# AUDIO_1.net
KiCad netlist of a schematic drawn in Altium Designer
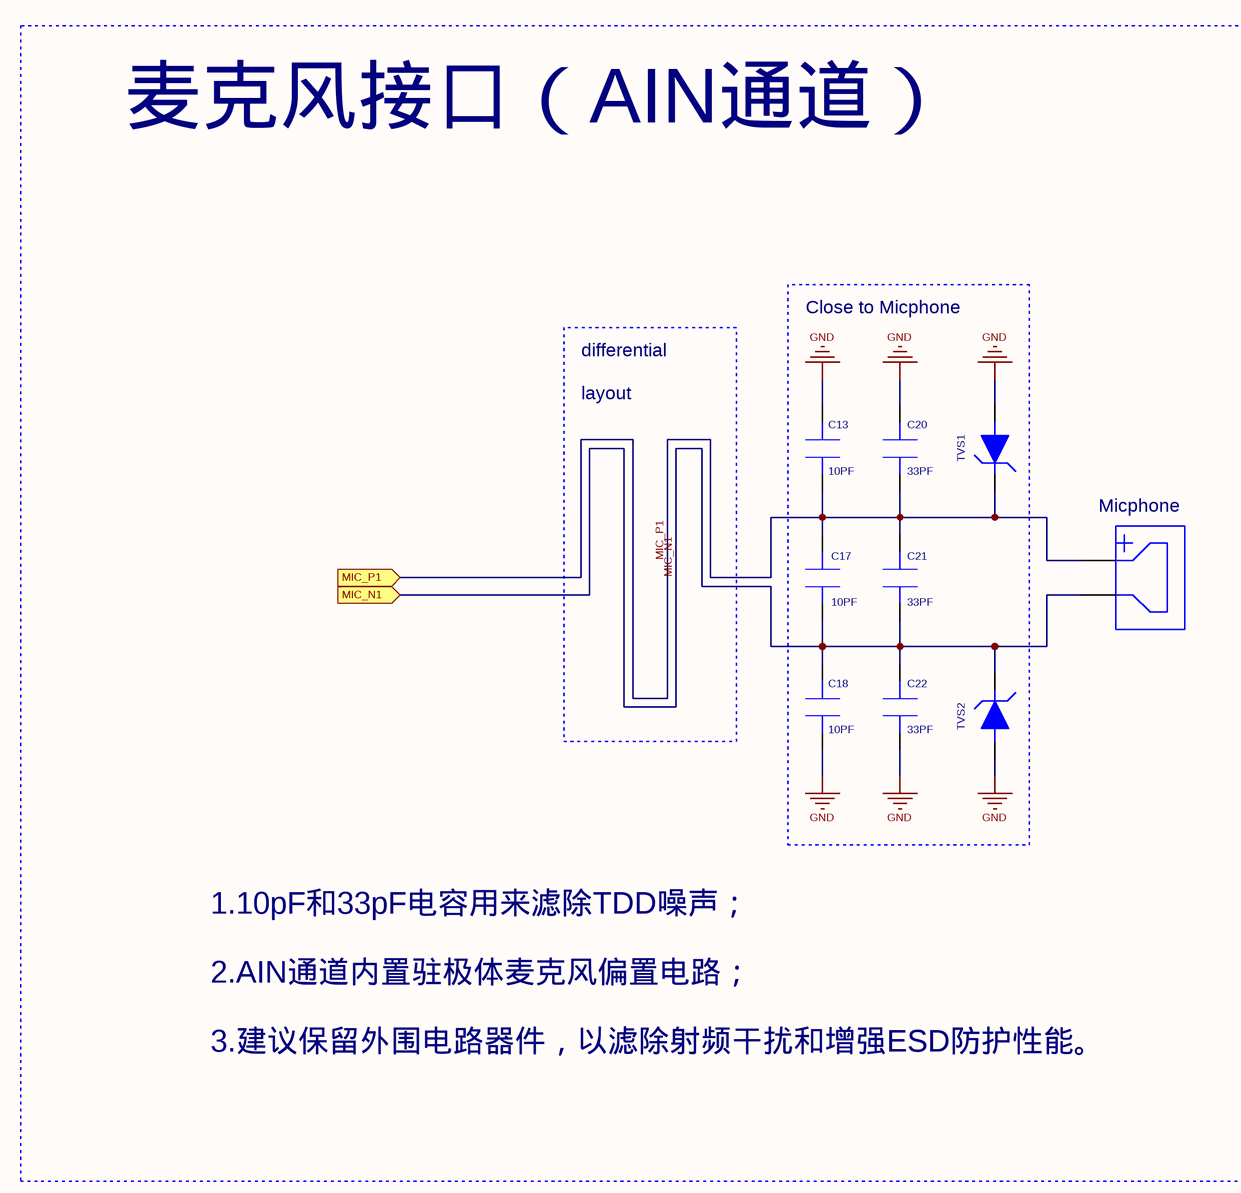
[diagram p0: AUDIO_1.SchDoc, top left]
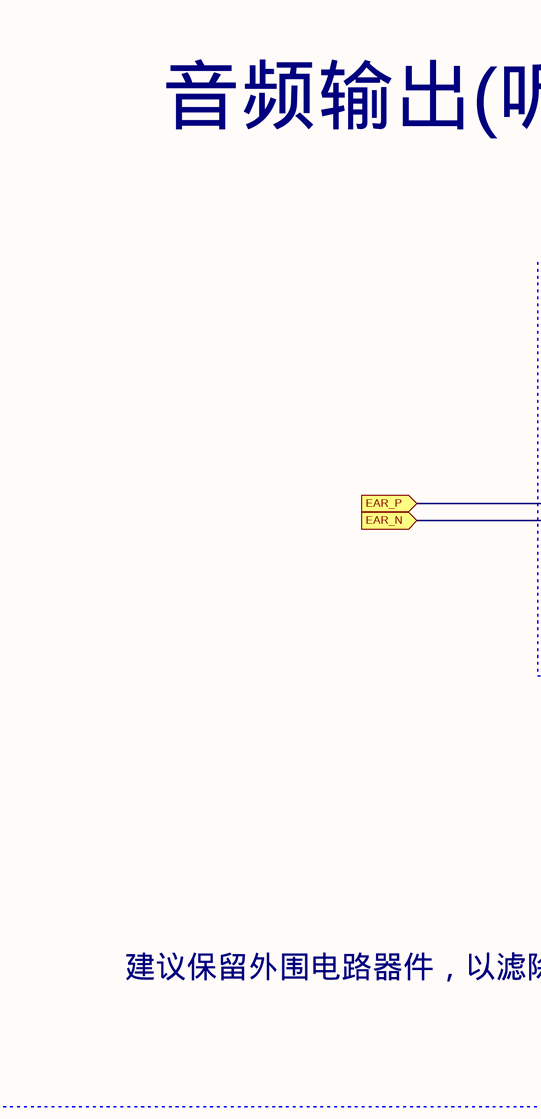
[diagram p1: AUDIO_1.SchDoc, top middle]
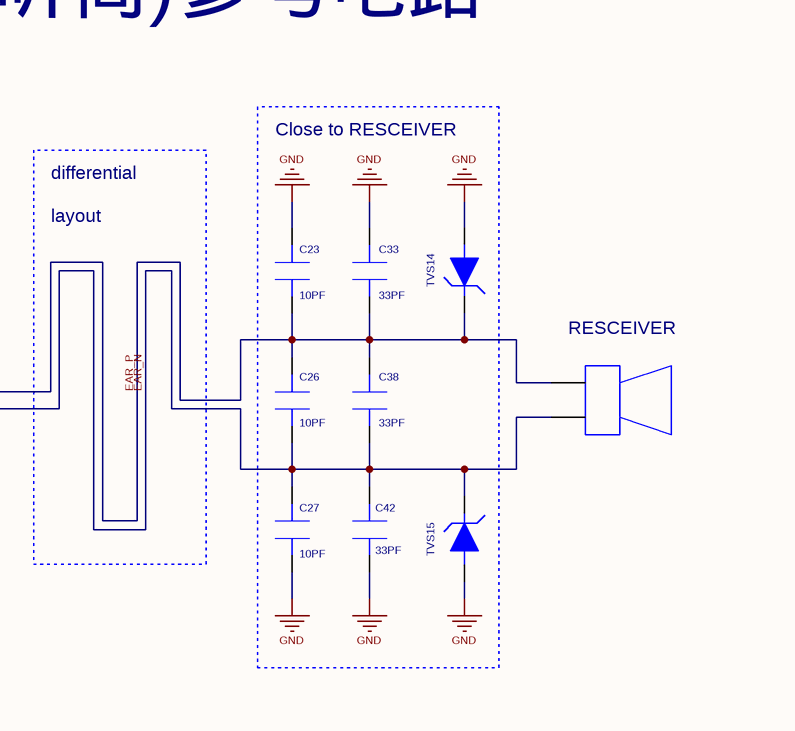
[diagram p2: AUDIO_1.SchDoc, top right]
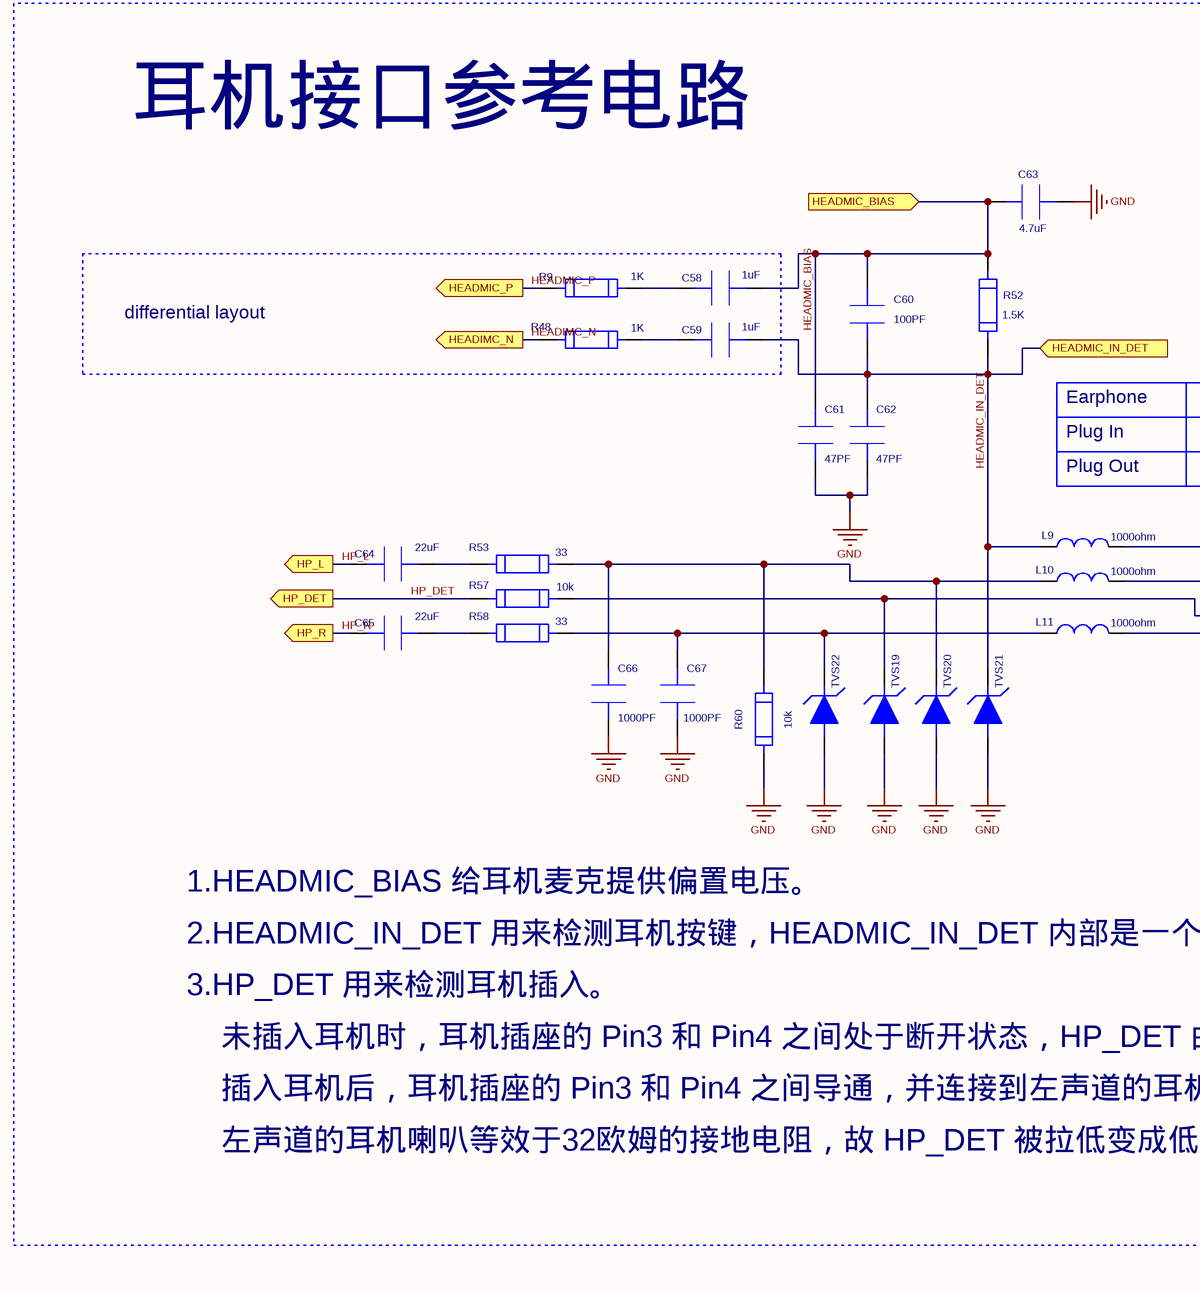
[diagram p3: AUDIO_1.SchDoc, bottom left]
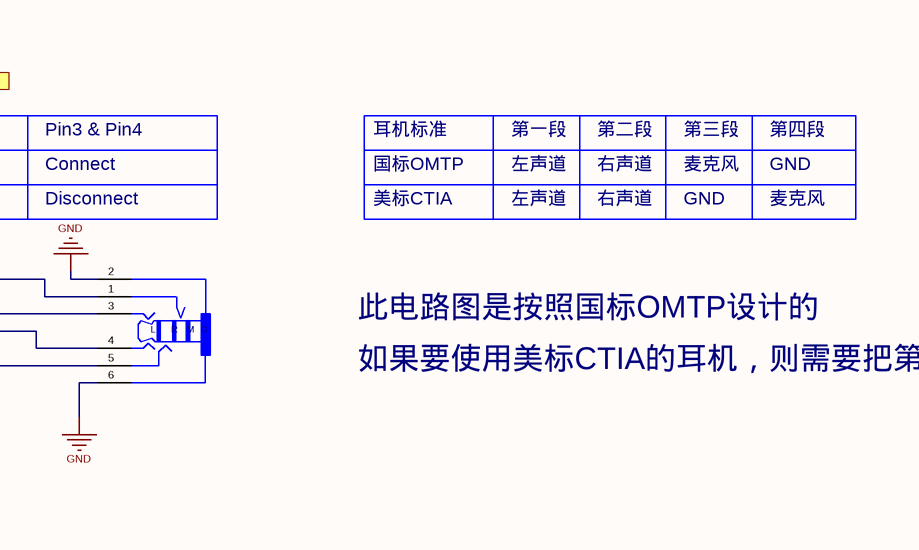
[diagram p4: AUDIO_1.SchDoc, bottom middle]
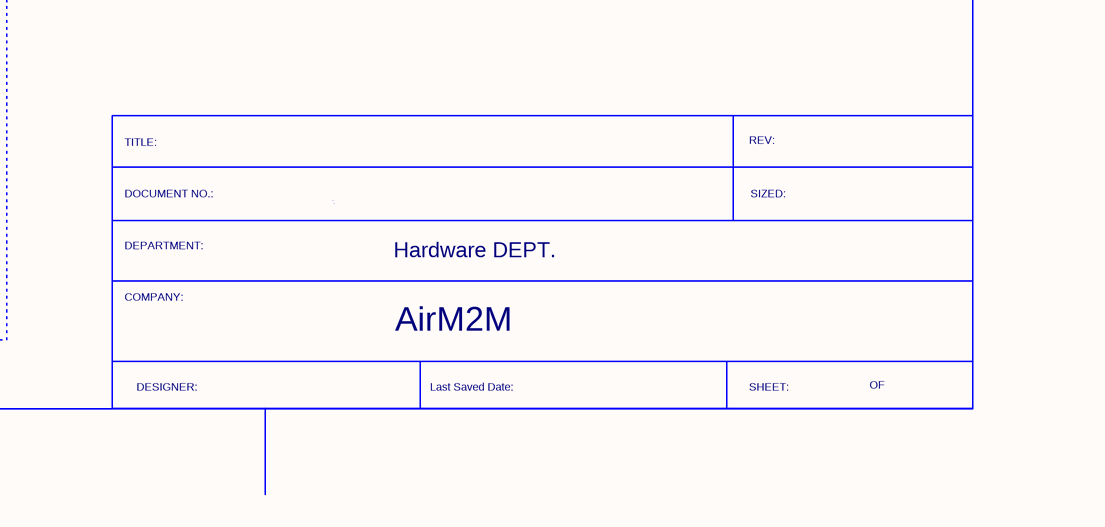
[diagram p5: AUDIO_1.SchDoc, bottom right]

(export (version "E")
  (design (tool "Eeschema 10.0.6"))
  (components
    (comp (ref "C13")
      (value "10PF")
      (footprint "SC0201")
      (description "CAP CER C0G;10PF;+/-5%;25V;0201;0.35mm;ROHS")
      (fields (field (name "TOLERANCE") "+/-5%") (field (name "Comment") "CAP-10PF-0201-COG"))
      (libsource (lib "*") (part "CAP-10PF-0201-COG"))
    )
    (comp (ref "C17")
      (value "10PF")
      (footprint "SC0201")
      (description "CAP CER C0G;10PF;+/-5%;25V;0201;0.35mm;ROHS")
      (fields (field (name "TOLERANCE") "+/-5%") (field (name "Comment") "CAP-10PF-0201-COG"))
      (libsource (lib "*") (part "CAP-10PF-0201-COG"))
    )
    (comp (ref "C18")
      (value "10PF")
      (footprint "SC0201")
      (description "CAP CER C0G;10PF;+/-5%;25V;0201;0.35mm;ROHS")
      (fields (field (name "TOLERANCE") "+/-5%") (field (name "Comment") "CAP-10PF-0201-COG"))
      (libsource (lib "*") (part "CAP-10PF-0201-COG"))
    )
    (comp (ref "C20")
      (value "33PF")
      (footprint "SC0201")
      (description "CAP CER C0G;10PF;+/-5%;25V;0201;0.35mm;ROHS")
      (fields (field (name "TOLERANCE") "+/-5%") (field (name "Comment") "CAP-10PF-0201-COG"))
      (libsource (lib "*") (part "CAP-10PF-0201-COG"))
    )
    (comp (ref "C21")
      (value "33PF")
      (footprint "SC0201")
      (description "CAP CER C0G;10PF;+/-5%;25V;0201;0.35mm;ROHS")
      (fields (field (name "TOLERANCE") "+/-5%") (field (name "Comment") "CAP-10PF-0201-COG"))
      (libsource (lib "*") (part "CAP-10PF-0201-COG"))
    )
    (comp (ref "C22")
      (value "33PF")
      (footprint "SC0201")
      (description "CAP CER C0G;10PF;+/-5%;25V;0201;0.35mm;ROHS")
      (fields (field (name "TOLERANCE") "+/-5%") (field (name "Comment") "CAP-10PF-0201-COG"))
      (libsource (lib "*") (part "CAP-10PF-0201-COG"))
    )
    (comp (ref "C23")
      (value "10PF")
      (footprint "SC0201")
      (description "CAP CER C0G;10PF;+/-5%;25V;0201;0.35mm;ROHS")
      (fields (field (name "TOLERANCE") "+/-5%") (field (name "Comment") "CAP-10PF-0201-COG"))
      (libsource (lib "*") (part "CAP-10PF-0201-COG"))
    )
    (comp (ref "C26")
      (value "10PF")
      (footprint "SC0201")
      (description "CAP CER C0G;10PF;+/-5%;25V;0201;0.35mm;ROHS")
      (fields (field (name "TOLERANCE") "+/-5%") (field (name "Comment") "CAP-10PF-0201-COG"))
      (libsource (lib "*") (part "CAP-10PF-0201-COG"))
    )
    (comp (ref "C27")
      (value "10PF")
      (footprint "SC0201")
      (description "CAP CER C0G;10PF;+/-5%;25V;0201;0.35mm;ROHS")
      (fields (field (name "TOLERANCE") "+/-5%") (field (name "Comment") "CAP-10PF-0201-COG"))
      (libsource (lib "*") (part "CAP-10PF-0201-COG"))
    )
    (comp (ref "C33")
      (value "33PF")
      (footprint "SC0201")
      (description "CAP CER C0G;10PF;+/-5%;25V;0201;0.35mm;ROHS")
      (fields (field (name "TOLERANCE") "+/-5%") (field (name "Comment") "CAP-10PF-0201-COG"))
      (libsource (lib "*") (part "CAP-10PF-0201-COG"))
    )
    (comp (ref "C38")
      (value "33PF")
      (footprint "SC0201")
      (description "CAP CER C0G;10PF;+/-5%;25V;0201;0.35mm;ROHS")
      (fields (field (name "TOLERANCE") "+/-5%") (field (name "Comment") "CAP-10PF-0201-COG"))
      (libsource (lib "*") (part "CAP-10PF-0201-COG"))
    )
    (comp (ref "C42")
      (value "33PF")
      (footprint "SC0201")
      (description "CAP CER C0G;10PF;+/-5%;25V;0201;0.35mm;ROHS")
      (fields (field (name "TOLERANCE") "+/-5%") (field (name "Comment") "CAP-10PF-0201-COG"))
      (libsource (lib "*") (part "CAP-10PF-0201-COG"))
    )
    (comp (ref "C58")
      (value "1uF")
      (footprint "SC0402")
      (description "CAP CER X5R;1uF;+/-10%;6.3V;0402;0.5mm;ROHS")
      (fields (field (name "TOLERANCE") "+/-10%") (field (name "Comment") "CAP-1UF-0402-X5R"))
      (libsource (lib "*") (part "CAP-1UF-0402-X5R"))
    )
    (comp (ref "C59")
      (value "1uF")
      (footprint "SC0402")
      (description "CAP CER X5R;1uF;+/-10%;6.3V;0402;0.5mm;ROHS")
      (fields (field (name "TOLERANCE") "+/-10%") (field (name "Comment") "CAP-1UF-0402-X5R"))
      (libsource (lib "*") (part "CAP-1UF-0402-X5R"))
    )
    (comp (ref "C60")
      (value "100PF")
      (footprint "SC0402")
      (description "CAP CER C0G;100PF;+/-5%;50V;0402;0.5mm;ROHS")
      (fields (field (name "TOLERANCE") "+/-5%") (field (name "Comment") "CAP-100PF-0402-C0G"))
      (libsource (lib "*") (part "CAP-100PF-0402-C0G"))
    )
    (comp (ref "C61")
      (value "47PF")
      (footprint "SC0402")
      (description "CAP CER C0G;47PF;+/-5%;50V;0402;0.5mm;ROHS")
      (fields (field (name "TOLERANCE") "+/-5%") (field (name "Comment") "CAP-47PF-0402-C0G"))
      (libsource (lib "*") (part "CAP-47PF-0402-C0G"))
    )
    (comp (ref "C62")
      (value "47PF")
      (footprint "SC0402")
      (description "CAP CER C0G;47PF;+/-5%;50V;0402;0.5mm;ROHS")
      (fields (field (name "TOLERANCE") "+/-5%") (field (name "Comment") "CAP-47PF-0402-C0G"))
      (libsource (lib "*") (part "CAP-47PF-0402-C0G"))
    )
    (comp (ref "C63")
      (value "4.7uF")
      (footprint "SC0402")
      (description "CAP CER;4.7uF;20%;6.3V;0402")
      (fields (field (name "TOLERANCE") "+/-20%") (field (name "Comment") "CAP-4.7UF-6.3V-0402"))
      (libsource (lib "*") (part "CAP-4.7UF-6.3V-0402"))
    )
    (comp (ref "C64")
      (value "22uF")
      (footprint "SC0402")
      (description "CAP CER;10uF;20%;6.3V")
      (fields (field (name "TOLERANCE") "+/-20%") (field (name "Comment") "CAP-10UF-6.3V-0402"))
      (libsource (lib "*") (part "CAP-10UF-6.3V-0402"))
    )
    (comp (ref "C65")
      (value "22uF")
      (footprint "SC0402")
      (description "CAP CER;10uF;20%;6.3V")
      (fields (field (name "TOLERANCE") "+/-20%") (field (name "Comment") "CAP-10UF-6.3V-0402"))
      (libsource (lib "*") (part "CAP-10UF-6.3V-0402"))
    )
    (comp (ref "C66")
      (value "1000PF")
      (footprint "SC0402")
      (description "CAP CER X7R;1000PF;+/-10%;50V;0402;0.5mm;ROHS")
      (fields (field (name "TOLERANCE") "+/-10%") (field (name "Comment") "CAP-1000PF-0402-X7R"))
      (libsource (lib "*") (part "CAP-1000PF-0402-X7R"))
    )
    (comp (ref "C67")
      (value "1000PF")
      (footprint "SC0402")
      (description "CAP CER X7R;1000PF;+/-10%;50V;0402;0.5mm;ROHS")
      (fields (field (name "TOLERANCE") "+/-10%") (field (name "Comment") "CAP-1000PF-0402-X7R"))
      (libsource (lib "*") (part "CAP-1000PF-0402-X7R"))
    )
    (comp (ref "J3")
      (value "AUDIO-SUGGEST-1")
      (footprint "AUDIO-EAR-DA0635180-1208-A")
      (description "耳机座")
      (libsource (lib "*") (part "AUDIO-SUGGEST-1"))
    )
    (comp (ref "J5")
      (value "AUDIO-SPEAKER-BLUEHY")
      (footprint "CON2-2")
      (libsource (lib "*") (part "AUDIO-SPEAKER-BLUEHY"))
    )
    (comp (ref "L9")
      (value "1000ohm")
      (footprint "SL0402")
      (description "Bead;1000ohm;250mA;0402;0.6mm;ROHS")
      (fields (field (name "Comment") "BEAD-1000OHM-0402"))
      (libsource (lib "*") (part "BEAD-1000OHM-0402"))
    )
    (comp (ref "L10")
      (value "1000ohm")
      (footprint "SL0402")
      (description "Bead;1000ohm;250mA;0402;0.6mm;ROHS")
      (fields (field (name "Comment") "BEAD-1000OHM-0402"))
      (libsource (lib "*") (part "BEAD-1000OHM-0402"))
    )
    (comp (ref "L11")
      (value "1000ohm")
      (footprint "SL0402")
      (description "Bead;1000ohm;250mA;0402;0.6mm;ROHS")
      (fields (field (name "Comment") "BEAD-1000OHM-0402"))
      (libsource (lib "*") (part "BEAD-1000OHM-0402"))
    )
    (comp (ref "M1")
      (value "AUDIO-MIC-BLUEHY")
      (footprint "CON2-2/3")
      (libsource (lib "*") (part "AUDIO-MIC-BLUEHY"))
    )
    (comp (ref "R9")
      (value "1K")
      (footprint "SR0402")
      (description "RES FILM;1K;+/-5%;1/16W;0402;0.4mm;ROHS")
      (fields (field (name "TOLERANCE") "+/-5%") (field (name "Comment") "RES-1K-0402"))
      (libsource (lib "*") (part "RES-1K-0402"))
    )
    (comp (ref "R48")
      (value "1K")
      (footprint "SR0402")
      (description "RES FILM;1K;+/-1%;1/16W;0402;0.4mm;ROHS")
      (fields (field (name "TOLERANCE") "+/-1%") (field (name "Comment") "RES-1K-+-1%-0402"))
      (libsource (lib "*") (part "RES-1K-+-1%-0402"))
    )
    (comp (ref "R52")
      (value "1.5K")
      (footprint "SR0402")
      (description "RES FILM;1.2k;+/-5%;1/16W;0402;0.4mm;ROHS")
      (fields (field (name "TOLERANCE") "5%") (field (name "Comment") "RES-1.2K-0402"))
      (libsource (lib "*") (part "RES-1.2K-0402"))
    )
    (comp (ref "R53")
      (value "33")
      (footprint "SR0402")
      (description "RES FILM;33;+/-5%;1/16W;0402;0.4mm;ROHS")
      (fields (field (name "TOLERANCE") "+/-5%") (field (name "Comment") "RES-33-0402"))
      (libsource (lib "*") (part "RES-33-0402"))
    )
    (comp (ref "R57")
      (value "10k")
      (footprint "SR0402")
      (description "RES FILM;10K;+/-5%;1/16W;0402;0.4mm;ROHS")
      (fields (field (name "TOLERANCE") "+/-5%") (field (name "Comment") "RES-10K-0402"))
      (libsource (lib "*") (part "RES-10K-0402"))
    )
    (comp (ref "R58")
      (value "33")
      (footprint "SR0402")
      (description "RES FILM;33;+/-5%;1/16W;0402;0.4mm;ROHS")
      (fields (field (name "TOLERANCE") "+/-5%") (field (name "Comment") "RES-33-0402"))
      (libsource (lib "*") (part "RES-33-0402"))
    )
    (comp (ref "R60")
      (value "10k")
      (footprint "SR0402")
      (description "RES FILM;10K;+/-5%;1/16W;0402;0.4mm;ROHS")
      (fields (field (name "TOLERANCE") "+/-5%") (field (name "Comment") "RES-10K-0402"))
      (libsource (lib "*") (part "RES-10K-0402"))
    )
    (comp (ref "TVS1")
      (value "ESD-TVS-ESD9X5.0ST5G")
      (footprint "SOD-923-ESD9X5.0ST5G")
      (description "TVS;5.0V;65PF;SOD?923;ROHS")
      (libsource (lib "*") (part "ESD-TVS-ESD9X5.0ST5G"))
    )
    (comp (ref "TVS2")
      (value "ESD-TVS-ESD9X5.0ST5G")
      (footprint "SOD-923-ESD9X5.0ST5G")
      (description "TVS;5.0V;65PF;SOD?923;ROHS")
      (libsource (lib "*") (part "ESD-TVS-ESD9X5.0ST5G"))
    )
    (comp (ref "TVS14")
      (value "ESD-TVS-ESD9X5.0ST5G")
      (footprint "SOD-923-ESD9X5.0ST5G")
      (description "TVS;5.0V;65PF;SOD?923;ROHS")
      (libsource (lib "*") (part "ESD-TVS-ESD9X5.0ST5G"))
    )
    (comp (ref "TVS15")
      (value "ESD-TVS-ESD9X5.0ST5G")
      (footprint "SOD-923-ESD9X5.0ST5G")
      (description "TVS;5.0V;65PF;SOD?923;ROHS")
      (libsource (lib "*") (part "ESD-TVS-ESD9X5.0ST5G"))
    )
    (comp (ref "TVS19")
      (value "ESD-TVS-ESD5Z5.0T1_A")
      (footprint "SOD523(ESD5Z5.0T1)")
      (description "TVS;5V;80pF;SOD-523;ROHS")
      (libsource (lib "*") (part "ESD-TVS-ESD5Z5.0T1_A"))
    )
    (comp (ref "TVS20")
      (value "ESD-TVS-ESD5Z5.0T1_A")
      (footprint "SOD523(ESD5Z5.0T1)")
      (description "TVS;5V;80pF;SOD-523;ROHS")
      (libsource (lib "*") (part "ESD-TVS-ESD5Z5.0T1_A"))
    )
    (comp (ref "TVS21")
      (value "ESD-TVS-ESD5Z5.0T1_A")
      (footprint "SOD523(ESD5Z5.0T1)")
      (description "TVS;5V;80pF;SOD-523;ROHS")
      (libsource (lib "*") (part "ESD-TVS-ESD5Z5.0T1_A"))
    )
    (comp (ref "TVS22")
      (value "ESD-TVS-ESD5Z5.0T1_A")
      (footprint "SOD523(ESD5Z5.0T1)")
      (description "TVS;5V;80pF;SOD-523;ROHS")
      (libsource (lib "*") (part "ESD-TVS-ESD5Z5.0T1_A"))
    )
  )
  (nets
    (net (code "1") (name "/EAR_N") (class "Default")
      (node (ref "C26") (pin "2") (pinfunction "2_2") (pintype "passive"))
      (node (ref "C27") (pin "1") (pinfunction "1_1") (pintype "passive"))
      (node (ref "C38") (pin "2") (pinfunction "2_2") (pintype "passive"))
      (node (ref "C42") (pin "1") (pinfunction "1_1") (pintype "passive"))
      (node (ref "J5") (pin "2") (pinfunction "2_2") (pintype "passive"))
      (node (ref "TVS15") (pin "1") (pinfunction "1_1") (pintype "passive"))
    )
    (net (code "2") (name "/EAR_P") (class "Default")
      (node (ref "C23") (pin "2") (pinfunction "2_2") (pintype "passive"))
      (node (ref "C26") (pin "1") (pinfunction "1_1") (pintype "passive"))
      (node (ref "C33") (pin "2") (pinfunction "2_2") (pintype "passive"))
      (node (ref "C38") (pin "1") (pinfunction "1_1") (pintype "passive"))
      (node (ref "J5") (pin "1") (pinfunction "1_1") (pintype "passive"))
      (node (ref "TVS14") (pin "1") (pinfunction "1_1") (pintype "passive"))
    )
    (net (code "3") (name "/HEADIMC_N") (class "Default")
      (node (ref "R48") (pin "1") (pinfunction "1_1") (pintype "passive"))
    )
    (net (code "4") (name "/HEADMIC_BIAS") (class "Default")
      (node (ref "C58") (pin "2") (pinfunction "2_2") (pintype "passive"))
      (node (ref "C60") (pin "1") (pinfunction "1_1") (pintype "passive"))
      (node (ref "C61") (pin "1") (pinfunction "1_1") (pintype "passive"))
      (node (ref "C63") (pin "1") (pinfunction "1_1") (pintype "passive"))
      (node (ref "R52") (pin "2") (pinfunction "2_2") (pintype "passive"))
    )
    (net (code "5") (name "/HEADMIC_IN_DET") (class "Default")
      (node (ref "C59") (pin "2") (pinfunction "2_2") (pintype "passive"))
      (node (ref "C60") (pin "2") (pinfunction "2_2") (pintype "passive"))
      (node (ref "C62") (pin "1") (pinfunction "1_1") (pintype "passive"))
      (node (ref "L9") (pin "1") (pinfunction "1_1") (pintype "passive"))
      (node (ref "R52") (pin "1") (pinfunction "1_1") (pintype "passive"))
      (node (ref "TVS21") (pin "1") (pinfunction "1_1") (pintype "passive"))
    )
    (net (code "6") (name "/HEADMIC_P") (class "Default")
      (node (ref "R9") (pin "1") (pinfunction "1_1") (pintype "passive"))
    )
    (net (code "7") (name "/HP_DET") (class "Default")
      (node (ref "R57") (pin "1") (pinfunction "1_1") (pintype "passive"))
    )
    (net (code "8") (name "/HP_L") (class "Default")
      (node (ref "C64") (pin "1") (pinfunction "1_1") (pintype "passive"))
    )
    (net (code "9") (name "/HP_R") (class "Default")
      (node (ref "C65") (pin "1") (pinfunction "1_1") (pintype "passive"))
    )
    (net (code "10") (name "/MIC_N1") (class "Default")
      (node (ref "C17") (pin "2") (pinfunction "2_2") (pintype "passive"))
      (node (ref "C18") (pin "1") (pinfunction "1_1") (pintype "passive"))
      (node (ref "C21") (pin "2") (pinfunction "2_2") (pintype "passive"))
      (node (ref "C22") (pin "1") (pinfunction "1_1") (pintype "passive"))
      (node (ref "M1") (pin "2") (pinfunction "2_2") (pintype "passive"))
      (node (ref "TVS2") (pin "1") (pinfunction "1_1") (pintype "passive"))
    )
    (net (code "11") (name "/MIC_P1") (class "Default")
      (node (ref "C13") (pin "2") (pinfunction "2_2") (pintype "passive"))
      (node (ref "C17") (pin "1") (pinfunction "1_1") (pintype "passive"))
      (node (ref "C20") (pin "2") (pinfunction "2_2") (pintype "passive"))
      (node (ref "C21") (pin "1") (pinfunction "1_1") (pintype "passive"))
      (node (ref "M1") (pin "1") (pinfunction "1_1") (pintype "passive"))
      (node (ref "TVS1") (pin "1") (pinfunction "1_1") (pintype "passive"))
    )
    (net (code "12") (name "GND") (class "Default")
      (node (ref "C13") (pin "1") (pinfunction "1_1") (pintype "passive"))
      (node (ref "C18") (pin "2") (pinfunction "2_2") (pintype "passive"))
      (node (ref "C20") (pin "1") (pinfunction "1_1") (pintype "passive"))
      (node (ref "C22") (pin "2") (pinfunction "2_2") (pintype "passive"))
      (node (ref "C23") (pin "1") (pinfunction "1_1") (pintype "passive"))
      (node (ref "C27") (pin "2") (pinfunction "2_2") (pintype "passive"))
      (node (ref "C33") (pin "1") (pinfunction "1_1") (pintype "passive"))
      (node (ref "C42") (pin "2") (pinfunction "2_2") (pintype "passive"))
      (node (ref "C61") (pin "2") (pinfunction "2_2") (pintype "passive"))
      (node (ref "C62") (pin "2") (pinfunction "2_2") (pintype "passive"))
      (node (ref "C63") (pin "2") (pinfunction "2_2") (pintype "passive"))
      (node (ref "C66") (pin "2") (pinfunction "2_2") (pintype "passive"))
      (node (ref "C67") (pin "2") (pinfunction "2_2") (pintype "passive"))
      (node (ref "J3") (pin "2") (pinfunction "2_2") (pintype "passive"))
      (node (ref "J3") (pin "6") (pinfunction "6_6") (pintype "passive"))
      (node (ref "R60") (pin "1") (pinfunction "1_1") (pintype "passive"))
      (node (ref "TVS1") (pin "2") (pinfunction "2_2") (pintype "passive"))
      (node (ref "TVS14") (pin "2") (pinfunction "2_2") (pintype "passive"))
      (node (ref "TVS15") (pin "2") (pinfunction "2_2") (pintype "passive"))
      (node (ref "TVS19") (pin "2") (pinfunction "2_2") (pintype "passive"))
      (node (ref "TVS2") (pin "2") (pinfunction "2_2") (pintype "passive"))
      (node (ref "TVS20") (pin "2") (pinfunction "2_2") (pintype "passive"))
      (node (ref "TVS21") (pin "2") (pinfunction "2_2") (pintype "passive"))
      (node (ref "TVS22") (pin "2") (pinfunction "2_2") (pintype "passive"))
    )
    (net (code "13") (name "Net-(C58-Pad1)") (class "Default")
      (node (ref "C58") (pin "1") (pinfunction "1_1") (pintype "passive"))
      (node (ref "R9") (pin "2") (pinfunction "2_2") (pintype "passive"))
    )
    (net (code "14") (name "Net-(C59-Pad1)") (class "Default")
      (node (ref "C59") (pin "1") (pinfunction "1_1") (pintype "passive"))
      (node (ref "R48") (pin "2") (pinfunction "2_2") (pintype "passive"))
    )
    (net (code "15") (name "Net-(C64-Pad2)") (class "Default")
      (node (ref "C64") (pin "2") (pinfunction "2_2") (pintype "passive"))
      (node (ref "R53") (pin "1") (pinfunction "1_1") (pintype "passive"))
    )
    (net (code "16") (name "Net-(C65-Pad2)") (class "Default")
      (node (ref "C65") (pin "2") (pinfunction "2_2") (pintype "passive"))
      (node (ref "R58") (pin "1") (pinfunction "1_1") (pintype "passive"))
    )
    (net (code "17") (name "Net-(C66-Pad1)") (class "Default")
      (node (ref "C66") (pin "1") (pinfunction "1_1") (pintype "passive"))
      (node (ref "L10") (pin "1") (pinfunction "1_1") (pintype "passive"))
      (node (ref "R53") (pin "2") (pinfunction "2_2") (pintype "passive"))
      (node (ref "R60") (pin "2") (pinfunction "2_2") (pintype "passive"))
      (node (ref "TVS20") (pin "1") (pinfunction "1_1") (pintype "passive"))
    )
    (net (code "18") (name "Net-(C67-Pad1)") (class "Default")
      (node (ref "C67") (pin "1") (pinfunction "1_1") (pintype "passive"))
      (node (ref "L11") (pin "1") (pinfunction "1_1") (pintype "passive"))
      (node (ref "R58") (pin "2") (pinfunction "2_2") (pintype "passive"))
      (node (ref "TVS22") (pin "1") (pinfunction "1_1") (pintype "passive"))
    )
    (net (code "19") (name "Net-(J3-Pad1)") (class "Default")
      (node (ref "J3") (pin "1") (pinfunction "1_1") (pintype "passive"))
      (node (ref "L9") (pin "2") (pinfunction "2_2") (pintype "passive"))
    )
    (net (code "20") (name "Net-(J3-Pad3)") (class "Default")
      (node (ref "J3") (pin "3") (pinfunction "3_3") (pintype "passive"))
      (node (ref "L10") (pin "2") (pinfunction "2_2") (pintype "passive"))
    )
    (net (code "21") (name "Net-(J3-Pad4)") (class "Default")
      (node (ref "J3") (pin "4") (pinfunction "4_4") (pintype "passive"))
      (node (ref "R57") (pin "2") (pinfunction "2_2") (pintype "passive"))
      (node (ref "TVS19") (pin "1") (pinfunction "1_1") (pintype "passive"))
    )
    (net (code "22") (name "Net-(J3-Pad5)") (class "Default")
      (node (ref "J3") (pin "5") (pinfunction "5_5") (pintype "passive"))
      (node (ref "L11") (pin "2") (pinfunction "2_2") (pintype "passive"))
    )
  )
)
